# Peripherals.net
KiCad netlist of a schematic drawn in Altium Designer
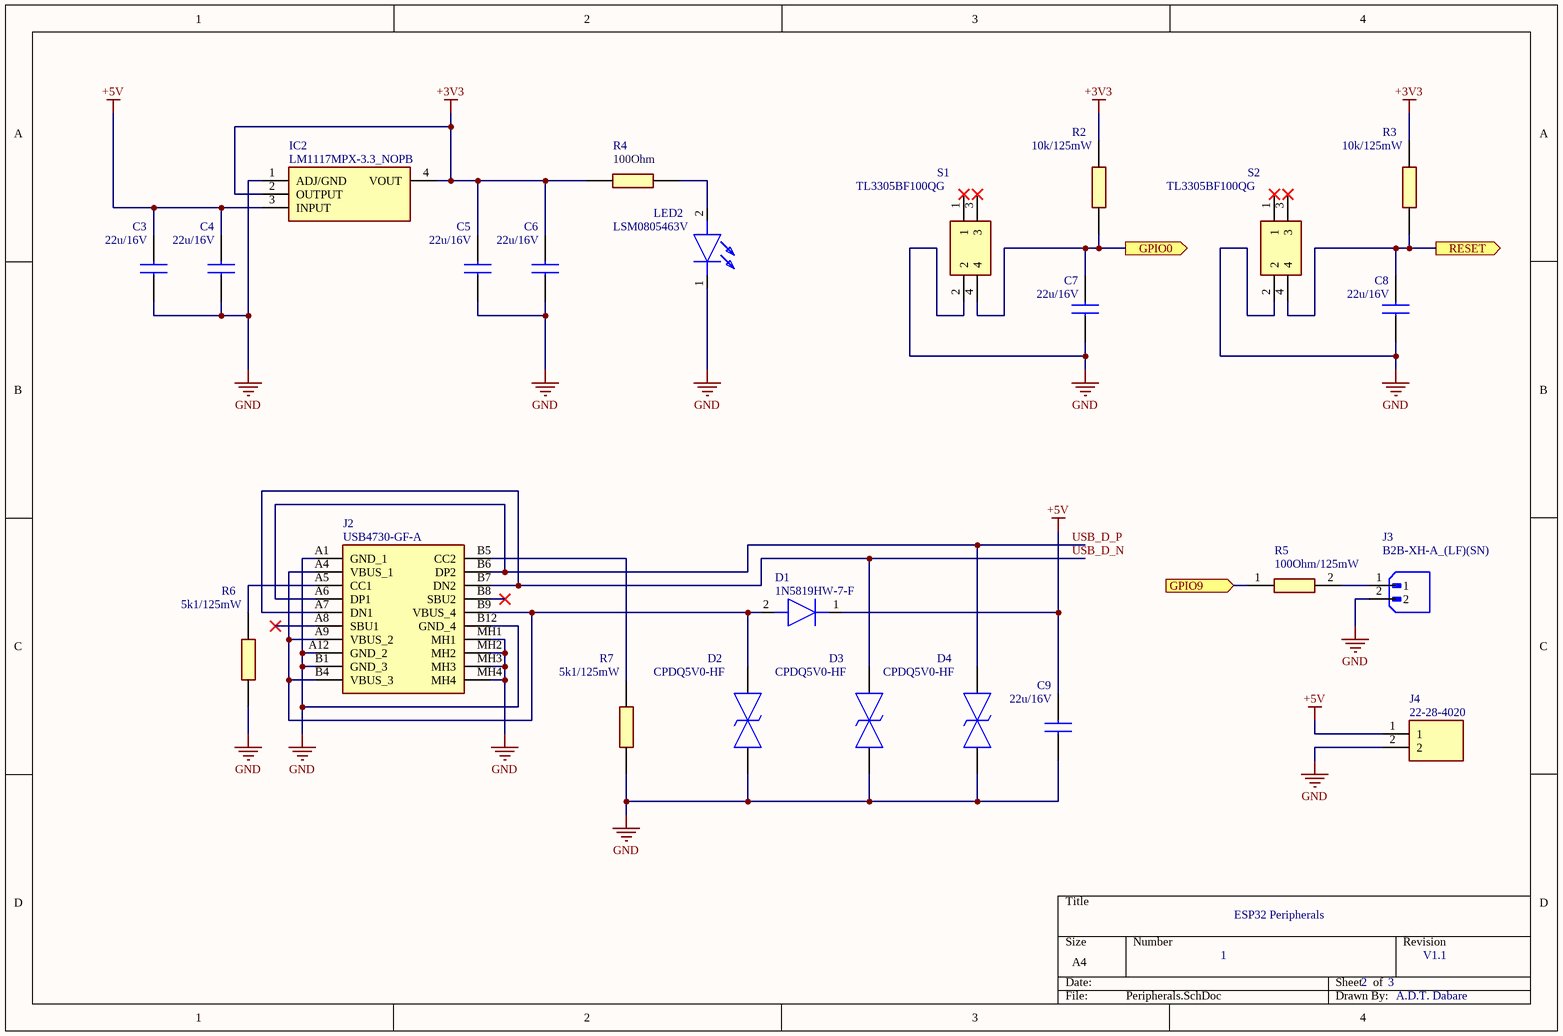
[diagram p0: Peripherals.SchDoc]

(export (version "E")
  (design (tool "Eeschema 10.0.6"))
  (components
    (comp (ref "C3")
      (value "22u/16V")
      (footprint "SamacSys:CAPC2012X94N")
      (fields
        (field (name "MANUFACTURER_PART_NUMBER") "0805YC106KAT2A")
        (field (name "MOUSER PART NUMBER") "581-0805YC106KAT2A")
      )
      (libsource (lib "*") (part "0805YC106KAT2A"))
    )
    (comp (ref "C4")
      (value "22u/16V")
      (footprint "SamacSys:C0805")
      (description "Multilayer Ceramic Capacitors MLCC - SMD/SMT 16V 0.1uF X7R 0805 10% Flex AEC-Q200")
      (fields
        (field (name "MANUFACTURER_PART_NUMBER") "C0805X104K4RACAUTO")
        (field (name "MOUSER PART NUMBER") "80-C0805X104K4RAUTO")
      )
      (libsource (lib "*") (part "C0805X104K4RACAUTO"))
    )
    (comp (ref "C5")
      (value "22u/16V")
      (footprint "SamacSys:CAPC2012X94N")
      (fields
        (field (name "MANUFACTURER_PART_NUMBER") "0805YC106KAT2A")
        (field (name "MOUSER PART NUMBER") "581-0805YC106KAT2A")
      )
      (libsource (lib "*") (part "0805YC106KAT2A"))
    )
    (comp (ref "C6")
      (value "22u/16V")
      (footprint "SamacSys:C0805")
      (description "Multilayer Ceramic Capacitors MLCC - SMD/SMT 16V 0.1uF X7R 0805 10% Flex AEC-Q200")
      (fields
        (field (name "MANUFACTURER_PART_NUMBER") "C0805X104K4RACAUTO")
        (field (name "MOUSER PART NUMBER") "80-C0805X104K4RAUTO")
      )
      (libsource (lib "*") (part "C0805X104K4RACAUTO"))
    )
    (comp (ref "C7")
      (value "22u/16V")
      (footprint "SamacSys:C0805")
      (description "Multilayer Ceramic Capacitors MLCC - SMD/SMT 16V 0.1uF X7R 0805 10% Flex AEC-Q200")
      (fields
        (field (name "MANUFACTURER_PART_NUMBER") "C0805X104K4RACAUTO")
        (field (name "MOUSER PART NUMBER") "80-C0805X104K4RAUTO")
      )
      (libsource (lib "*") (part "C0805X104K4RACAUTO"))
    )
    (comp (ref "C8")
      (value "22u/16V")
      (footprint "SamacSys:C0805")
      (description "Multilayer Ceramic Capacitors MLCC - SMD/SMT 16V 0.1uF X7R 0805 10% Flex AEC-Q200")
      (fields
        (field (name "MANUFACTURER_PART_NUMBER") "C0805X104K4RACAUTO")
        (field (name "MOUSER PART NUMBER") "80-C0805X104K4RAUTO")
      )
      (libsource (lib "*") (part "C0805X104K4RACAUTO"))
    )
    (comp (ref "C9")
      (value "22u/16V")
      (footprint "SamacSys:CAPC2012X94N")
      (fields
        (field (name "MANUFACTURER_PART_NUMBER") "0805YC106KAT2A")
        (field (name "MOUSER PART NUMBER") "581-0805YC106KAT2A")
      )
      (libsource (lib "*") (part "0805YC106KAT2A"))
    )
    (comp (ref "D1")
      (value "1N5819HW-7-F")
      (footprint "SamacSys:SOD3716X145N")
      (description "Schottky Diodes & Rectifiers Vr/40V Io/1A T/R")
      (fields (field (name "MOUSER PART NUMBER") "621-1N5819HW-F"))
      (libsource (lib "*") (part "1N5819HW-7-F"))
    )
    (comp (ref "D2")
      (value "CPDQ5V0-HF")
      (footprint "SamacSys:SODFL1006X40N")
      (description "ESD Protection Diodes / TVS Diodes SMD ESD Diode 5V Bi-Direction")
      (fields (field (name "MOUSER PART NUMBER") "750-CPDQ5V0-HF"))
      (libsource (lib "*") (part "CPDQ5V0-HF"))
    )
    (comp (ref "D3")
      (value "CPDQ5V0-HF")
      (footprint "SamacSys:SODFL1006X40N")
      (description "ESD Protection Diodes / TVS Diodes SMD ESD Diode 5V Bi-Direction")
      (fields (field (name "MOUSER PART NUMBER") "750-CPDQ5V0-HF"))
      (libsource (lib "*") (part "CPDQ5V0-HF"))
    )
    (comp (ref "D4")
      (value "CPDQ5V0-HF")
      (footprint "SamacSys:SODFL1006X40N")
      (description "ESD Protection Diodes / TVS Diodes SMD ESD Diode 5V Bi-Direction")
      (fields (field (name "MOUSER PART NUMBER") "750-CPDQ5V0-HF"))
      (libsource (lib "*") (part "CPDQ5V0-HF"))
    )
    (comp (ref "IC2")
      (value "LM1117MPX-3.3_NOPB")
      (footprint "SamacSys:SOT230P700X180-4N")
      (description "LDO Voltage Regulators 800MA LDO LINEAR REG")
      (fields
        (field (name "MANUFACTURER_PART_NUMBER") "LM1117MPX-3.3/NOPB")
        (field (name "MOUSER PART NUMBER") "926-LM1117MPX3.3NOPB")
      )
      (libsource (lib "*") (part "LM1117MPX-3.3_NOPB"))
    )
    (comp (ref "J2")
      (value "USB4730-GF-A")
      (footprint "SamacSys:USB4730GFA")
      (description "USB Connectors USB2.0 TypeC Recpt. CONNECTOR ONLY GF, 16P Horz T.Mt. SMT, IP67")
      (fields (field (name "MOUSER PART NUMBER") "640-USB4730GFA"))
      (libsource (lib "*") (part "USB4730-GF-A"))
    )
    (comp (ref "J3")
      (value "B2B-XH-A_(LF)(SN)")
      (footprint "JST_B2B-XH-A_(LF)(SN)")
      (description "Connector Header Through Hole 2 position 0.098 (2.50mm)")
      (fields (field (name "MF") "JST Sales") (field (name "MP") "B2B-XH-A (LF)(SN)"))
      (libsource (lib "B2B-XH-A__LF__SN_") (part "B2B-XH-A_(LF)(SN)"))
    )
    (comp (ref "J4")
      (value "22-28-4020")
      (footprint "SamacSys:HDRV2W66P0X254_1X2_508X249X838P")
      (description "Connector")
      (fields (field (name "MOUSER PART NUMBER") "538-22-28-4020"))
      (libsource (lib "*") (part "22-28-4020"))
    )
    (comp (ref "LED2")
      (value "LSM0805463V")
      (footprint "SamacSys:LEDC2012X90N")
      (description "Standard LEDs - SMD 0805 3V 100mcd Blue")
      (fields (field (name "MOUSER PART NUMBER") "593-LSM0805463V"))
      (libsource (lib "*") (part "LSM0805463V"))
    )
    (comp (ref "R2")
      (value "10k/125mW")
      (footprint "SamacSys:ERA6AEB101V")
      (description "Thin Film Resistors - SMD 0805 10Kohm 0.1% 15ppm AEC-Q200")
      (fields
        (field (name "MANUFACTURER_PART_NUMBER") "ERA-6APB103V")
        (field (name "MOUSER PART NUMBER") "667-ERA-6APB103V")
      )
      (libsource (lib "*") (part "ERA-6APB103V"))
    )
    (comp (ref "R3")
      (value "10k/125mW")
      (footprint "SamacSys:ERA6AEB101V")
      (description "Thin Film Resistors - SMD 0805 10Kohm 0.1% 15ppm AEC-Q200")
      (fields
        (field (name "MANUFACTURER_PART_NUMBER") "ERA-6APB103V")
        (field (name "MOUSER PART NUMBER") "667-ERA-6APB103V")
      )
      (libsource (lib "*") (part "ERA-6APB103V"))
    )
    (comp (ref "R4")
      (value "100Ohm")
      (footprint "SamacSys:ERA6AEB101V")
      (description "Thin Film Resistors - SMD 0805 12ohms 50ppm 0.5% AEC-Q200")
      (fields
        (field (name "MANUFACTURER_PART_NUMBER") "ERA-6AHD120V")
        (field (name "MOUSER PART NUMBER") "667-ERA-6AHD120V")
      )
      (libsource (lib "*") (part "ERA-6AHD120V"))
    )
    (comp (ref "R5")
      (value "100Ohm/125mW")
      (footprint "SamacSys:ERA6AEB101V")
      (description "Thin Film Resistors - SMD 0805 56ohms 25ppm 0.5% AEC-Q200")
      (fields (field (name "MANUFACTURER_PART_NUMBER") "ERA-6AED560V"))
      (libsource (lib "*") (part "ERA-6AED560V"))
    )
    (comp (ref "R6")
      (value "5k1/125mW")
      (footprint "SamacSys:ERA6AEB101V")
      (description "Thin Film Resistors - SMD 0805 5100ohms 25ppm 0.5% AEC-Q200")
      (fields
        (field (name "MANUFACTURER_PART_NUMBER") "ERA-6AED512V")
        (field (name "MOUSER PART NUMBER") "667-ERA-6AED512V")
      )
      (libsource (lib "*") (part "ERA-6AED512V"))
    )
    (comp (ref "R7")
      (value "5k1/125mW")
      (footprint "SamacSys:ERA6AEB101V")
      (description "Thin Film Resistors - SMD 0805 5100ohms 25ppm 0.5% AEC-Q200")
      (fields
        (field (name "MANUFACTURER_PART_NUMBER") "ERA-6AED512V")
        (field (name "MOUSER PART NUMBER") "667-ERA-6AED512V")
      )
      (libsource (lib "*") (part "ERA-6AED512V"))
    )
    (comp (ref "S1")
      (value "TL3305BF100QG")
      (footprint "SamacSys:TL3305BF160QG")
      (description "Tactile Switches TACT, 50mA, SPST-NO, Surface Mount")
      (libsource (lib "*") (part "TL3305BF100QG"))
    )
    (comp (ref "S2")
      (value "TL3305BF100QG")
      (footprint "SamacSys:TL3305BF160QG")
      (description "Tactile Switches TACT, 50mA, SPST-NO, Surface Mount")
      (libsource (lib "*") (part "TL3305BF100QG"))
    )
  )
  (nets
    (net (code "1") (name "+3V3") (class "Default")
      (node (ref "C5") (pin "1") (pinfunction "1_1") (pintype "passive"))
      (node (ref "C6") (pin "1") (pinfunction "1_1") (pintype "passive"))
      (node (ref "IC2") (pin "2") (pinfunction "OUTPUT_2") (pintype "passive"))
      (node (ref "IC2") (pin "4") (pinfunction "VOUT_4") (pintype "passive"))
      (node (ref "R2") (pin "2") (pinfunction "2_2") (pintype "passive"))
      (node (ref "R3") (pin "2") (pinfunction "2_2") (pintype "passive"))
      (node (ref "R4") (pin "1") (pinfunction "1_1") (pintype "passive"))
    )
    (net (code "2") (name "+5V") (class "Default")
      (node (ref "C3") (pin "1") (pinfunction "1_1") (pintype "passive"))
      (node (ref "C4") (pin "1") (pinfunction "1_1") (pintype "passive"))
      (node (ref "C9") (pin "1") (pinfunction "1_1") (pintype "passive"))
      (node (ref "D1") (pin "1") (pinfunction "K_1") (pintype "passive"))
      (node (ref "IC2") (pin "3") (pinfunction "INPUT_3") (pintype "passive"))
      (node (ref "J4") (pin "1") (pinfunction "1_1") (pintype "passive"))
    )
    (net (code "3") (name "/GPIO0") (class "Default")
      (node (ref "C7") (pin "1") (pinfunction "1_1") (pintype "passive"))
      (node (ref "R2") (pin "1") (pinfunction "1_1") (pintype "passive"))
      (node (ref "S1") (pin "4") (pinfunction "4_4") (pintype "passive"))
    )
    (net (code "4") (name "/GPIO9") (class "Default")
      (node (ref "R5") (pin "1") (pinfunction "1_1") (pintype "passive"))
    )
    (net (code "5") (name "/RESET") (class "Default")
      (node (ref "C8") (pin "1") (pinfunction "1_1") (pintype "passive"))
      (node (ref "R3") (pin "1") (pinfunction "1_1") (pintype "passive"))
      (node (ref "S2") (pin "4") (pinfunction "4_4") (pintype "passive"))
    )
    (net (code "6") (name "/USB_D_N") (class "Default")
      (node (ref "D3") (pin "1") (pinfunction "1_1") (pintype "passive"))
      (node (ref "J2") (pin "A7") (pinfunction "DN1_A7") (pintype "passive"))
      (node (ref "J2") (pin "B7") (pinfunction "DN2_B7") (pintype "passive"))
    )
    (net (code "7") (name "/USB_D_P") (class "Default")
      (node (ref "D4") (pin "1") (pinfunction "1_1") (pintype "passive"))
      (node (ref "J2") (pin "A6") (pinfunction "DP1_A6") (pintype "passive"))
      (node (ref "J2") (pin "B6") (pinfunction "DP2_B6") (pintype "passive"))
    )
    (net (code "8") (name "GND") (class "Default")
      (node (ref "C3") (pin "2") (pinfunction "2_2") (pintype "passive"))
      (node (ref "C4") (pin "2") (pinfunction "2_2") (pintype "passive"))
      (node (ref "C5") (pin "2") (pinfunction "2_2") (pintype "passive"))
      (node (ref "C6") (pin "2") (pinfunction "2_2") (pintype "passive"))
      (node (ref "C7") (pin "2") (pinfunction "2_2") (pintype "passive"))
      (node (ref "C8") (pin "2") (pinfunction "2_2") (pintype "passive"))
      (node (ref "C9") (pin "2") (pinfunction "2_2") (pintype "passive"))
      (node (ref "D2") (pin "2") (pinfunction "2_2") (pintype "passive"))
      (node (ref "D3") (pin "2") (pinfunction "2_2") (pintype "passive"))
      (node (ref "D4") (pin "2") (pinfunction "2_2") (pintype "passive"))
      (node (ref "IC2") (pin "1") (pinfunction "ADJ/GND_1") (pintype "passive"))
      (node (ref "J2") (pin "A1") (pinfunction "GND_1_A1") (pintype "passive"))
      (node (ref "J2") (pin "A12") (pinfunction "GND_2_A12") (pintype "passive"))
      (node (ref "J2") (pin "B1") (pinfunction "GND_3_B1") (pintype "passive"))
      (node (ref "J2") (pin "B12") (pinfunction "GND_4_B12") (pintype "passive"))
      (node (ref "J2") (pin "MH1") (pinfunction "MH1_MH1") (pintype "passive"))
      (node (ref "J2") (pin "MH2") (pinfunction "MH2_MH2") (pintype "passive"))
      (node (ref "J2") (pin "MH3") (pinfunction "MH3_MH3") (pintype "passive"))
      (node (ref "J2") (pin "MH4") (pinfunction "MH4_MH4") (pintype "passive"))
      (node (ref "J3") (pin "2") (pinfunction "2_2") (pintype "passive"))
      (node (ref "J4") (pin "2") (pinfunction "2_2") (pintype "passive"))
      (node (ref "LED2") (pin "1") (pinfunction "K_1") (pintype "passive"))
      (node (ref "R6") (pin "2") (pinfunction "2_2") (pintype "passive"))
      (node (ref "R7") (pin "2") (pinfunction "2_2") (pintype "passive"))
      (node (ref "S1") (pin "2") (pinfunction "2_2") (pintype "passive"))
      (node (ref "S2") (pin "2") (pinfunction "2_2") (pintype "passive"))
    )
    (net (code "9") (name "Net-(D1-A)") (class "Default")
      (node (ref "D1") (pin "2") (pinfunction "A_2") (pintype "passive"))
      (node (ref "D2") (pin "1") (pinfunction "1_1") (pintype "passive"))
      (node (ref "J2") (pin "A4") (pinfunction "VBUS_1_A4") (pintype "passive"))
      (node (ref "J2") (pin "A9") (pinfunction "VBUS_2_A9") (pintype "passive"))
      (node (ref "J2") (pin "B4") (pinfunction "VBUS_3_B4") (pintype "passive"))
      (node (ref "J2") (pin "B9") (pinfunction "VBUS_4_B9") (pintype "passive"))
    )
    (net (code "10") (name "Net-(J2-CC1)") (class "Default")
      (node (ref "J2") (pin "A5") (pinfunction "CC1_A5") (pintype "passive"))
      (node (ref "R6") (pin "1") (pinfunction "1_1") (pintype "passive"))
    )
    (net (code "11") (name "Net-(J2-CC2)") (class "Default")
      (node (ref "J2") (pin "B5") (pinfunction "CC2_B5") (pintype "passive"))
      (node (ref "R7") (pin "1") (pinfunction "1_1") (pintype "passive"))
    )
    (net (code "12") (name "Net-(J3-Pad1)") (class "Default")
      (node (ref "J3") (pin "1") (pinfunction "1_1") (pintype "passive"))
      (node (ref "R5") (pin "2") (pinfunction "2_2") (pintype "passive"))
    )
    (net (code "13") (name "Net-(LED2-A)") (class "Default")
      (node (ref "LED2") (pin "2") (pinfunction "A_2") (pintype "passive"))
      (node (ref "R4") (pin "2") (pinfunction "2_2") (pintype "passive"))
    )
    (net (code "14") (name "unconnected-(J2-SBU1-PadA8)") (class "Default")
      (node (ref "J2") (pin "A8") (pinfunction "SBU1_A8") (pintype "passive+no_connect"))
    )
    (net (code "15") (name "unconnected-(J2-SBU2-PadB8)") (class "Default")
      (node (ref "J2") (pin "B8") (pinfunction "SBU2_B8") (pintype "passive+no_connect"))
    )
    (net (code "16") (name "unconnected-(S1-Pad1)") (class "Default")
      (node (ref "S1") (pin "1") (pinfunction "1_1") (pintype "passive+no_connect"))
    )
    (net (code "17") (name "unconnected-(S1-Pad3)") (class "Default")
      (node (ref "S1") (pin "3") (pinfunction "3_3") (pintype "passive+no_connect"))
    )
    (net (code "18") (name "unconnected-(S2-Pad1)") (class "Default")
      (node (ref "S2") (pin "1") (pinfunction "1_1") (pintype "passive+no_connect"))
    )
    (net (code "19") (name "unconnected-(S2-Pad3)") (class "Default")
      (node (ref "S2") (pin "3") (pinfunction "3_3") (pintype "passive+no_connect"))
    )
  )
)
